# Top_Sheet.net
KiCad netlist of a schematic drawn in Altium Designer
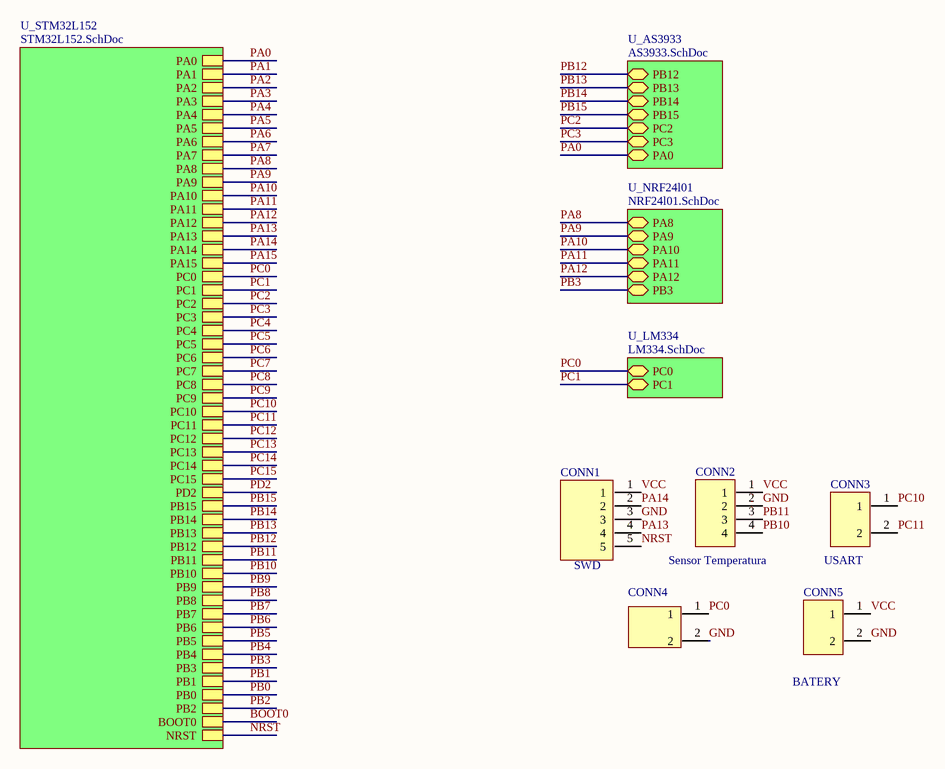
[diagram p0: Top Sheet.SchDoc]

(export (version "E")
  (design (tool "Eeschema 10.0.6"))
  (components
    (comp (ref "CONN1")
      (value "SWD")
      (footprint "1x5x2.54 Pin Header TH V")
      (libsource (lib "Tesis") (part "Header 1x5"))
    )
    (comp (ref "CONN2")
      (value "Sensor Temperatura")
      (footprint "1x4x2.54 Pin Header TH V")
      (libsource (lib "Tesis") (part "Header 1x4"))
    )
    (comp (ref "CONN3")
      (value "USART")
      (footprint "1x2x2.54 Pin Header TH V")
      (libsource (lib "Tesis") (part "Header 1x2"))
    )
    (comp (ref "CONN4")
      (value "Connector")
      (footprint "1x2x2.54 Pin Header TH V - duplicate")
      (libsource (lib "Schlib1") (part "Header 1x2"))
    )
    (comp (ref "CONN5")
      (value "BATERY")
      (footprint "1x2X2.54 Horizontal")
      (libsource (lib "Tesis") (part "Header 1x2"))
    )
  )
  (nets
    (net (code "2") (name "/GND") (class "Default")
      (node (ref "CONN1") (pin "3") (pinfunction "3_3") (pintype "passive"))
      (node (ref "CONN2") (pin "2") (pinfunction "2_2") (pintype "passive"))
      (node (ref "CONN4") (pin "2") (pinfunction "2_2") (pintype "passive"))
      (node (ref "CONN5") (pin "2") (pinfunction "2_2") (pintype "passive"))
    )
    (net (code "3") (name "/NRST") (class "Default")
      (node (ref "CONN1") (pin "5") (pinfunction "5_5") (pintype "passive"))
    )
    (net (code "17") (name "/PA13") (class "Default")
      (node (ref "CONN1") (pin "4") (pinfunction "4_4") (pintype "passive"))
    )
    (net (code "18") (name "/PA14") (class "Default")
      (node (ref "CONN1") (pin "2") (pinfunction "2_2") (pintype "passive"))
    )
    (net (code "30") (name "/PB10") (class "Default")
      (node (ref "CONN2") (pin "4") (pinfunction "4_4") (pintype "passive"))
    )
    (net (code "31") (name "/PB11") (class "Default")
      (node (ref "CONN2") (pin "3") (pinfunction "3_3") (pintype "passive"))
    )
    (net (code "36") (name "/PC0") (class "Default")
      (node (ref "CONN4") (pin "1") (pinfunction "1_1") (pintype "passive"))
    )
    (net (code "46") (name "/PC10") (class "Default")
      (node (ref "CONN3") (pin "1") (pinfunction "1_1") (pintype "passive"))
    )
    (net (code "47") (name "/PC11") (class "Default")
      (node (ref "CONN3") (pin "2") (pinfunction "2_2") (pintype "passive"))
    )
    (net (code "53") (name "/VCC") (class "Default")
      (node (ref "CONN1") (pin "1") (pinfunction "1_1") (pintype "passive"))
      (node (ref "CONN2") (pin "1") (pinfunction "1_1") (pintype "passive"))
      (node (ref "CONN5") (pin "1") (pinfunction "1_1") (pintype "passive"))
    )
  )
)
